# Display_Port.net
KiCad netlist of a schematic drawn in Altium Designer
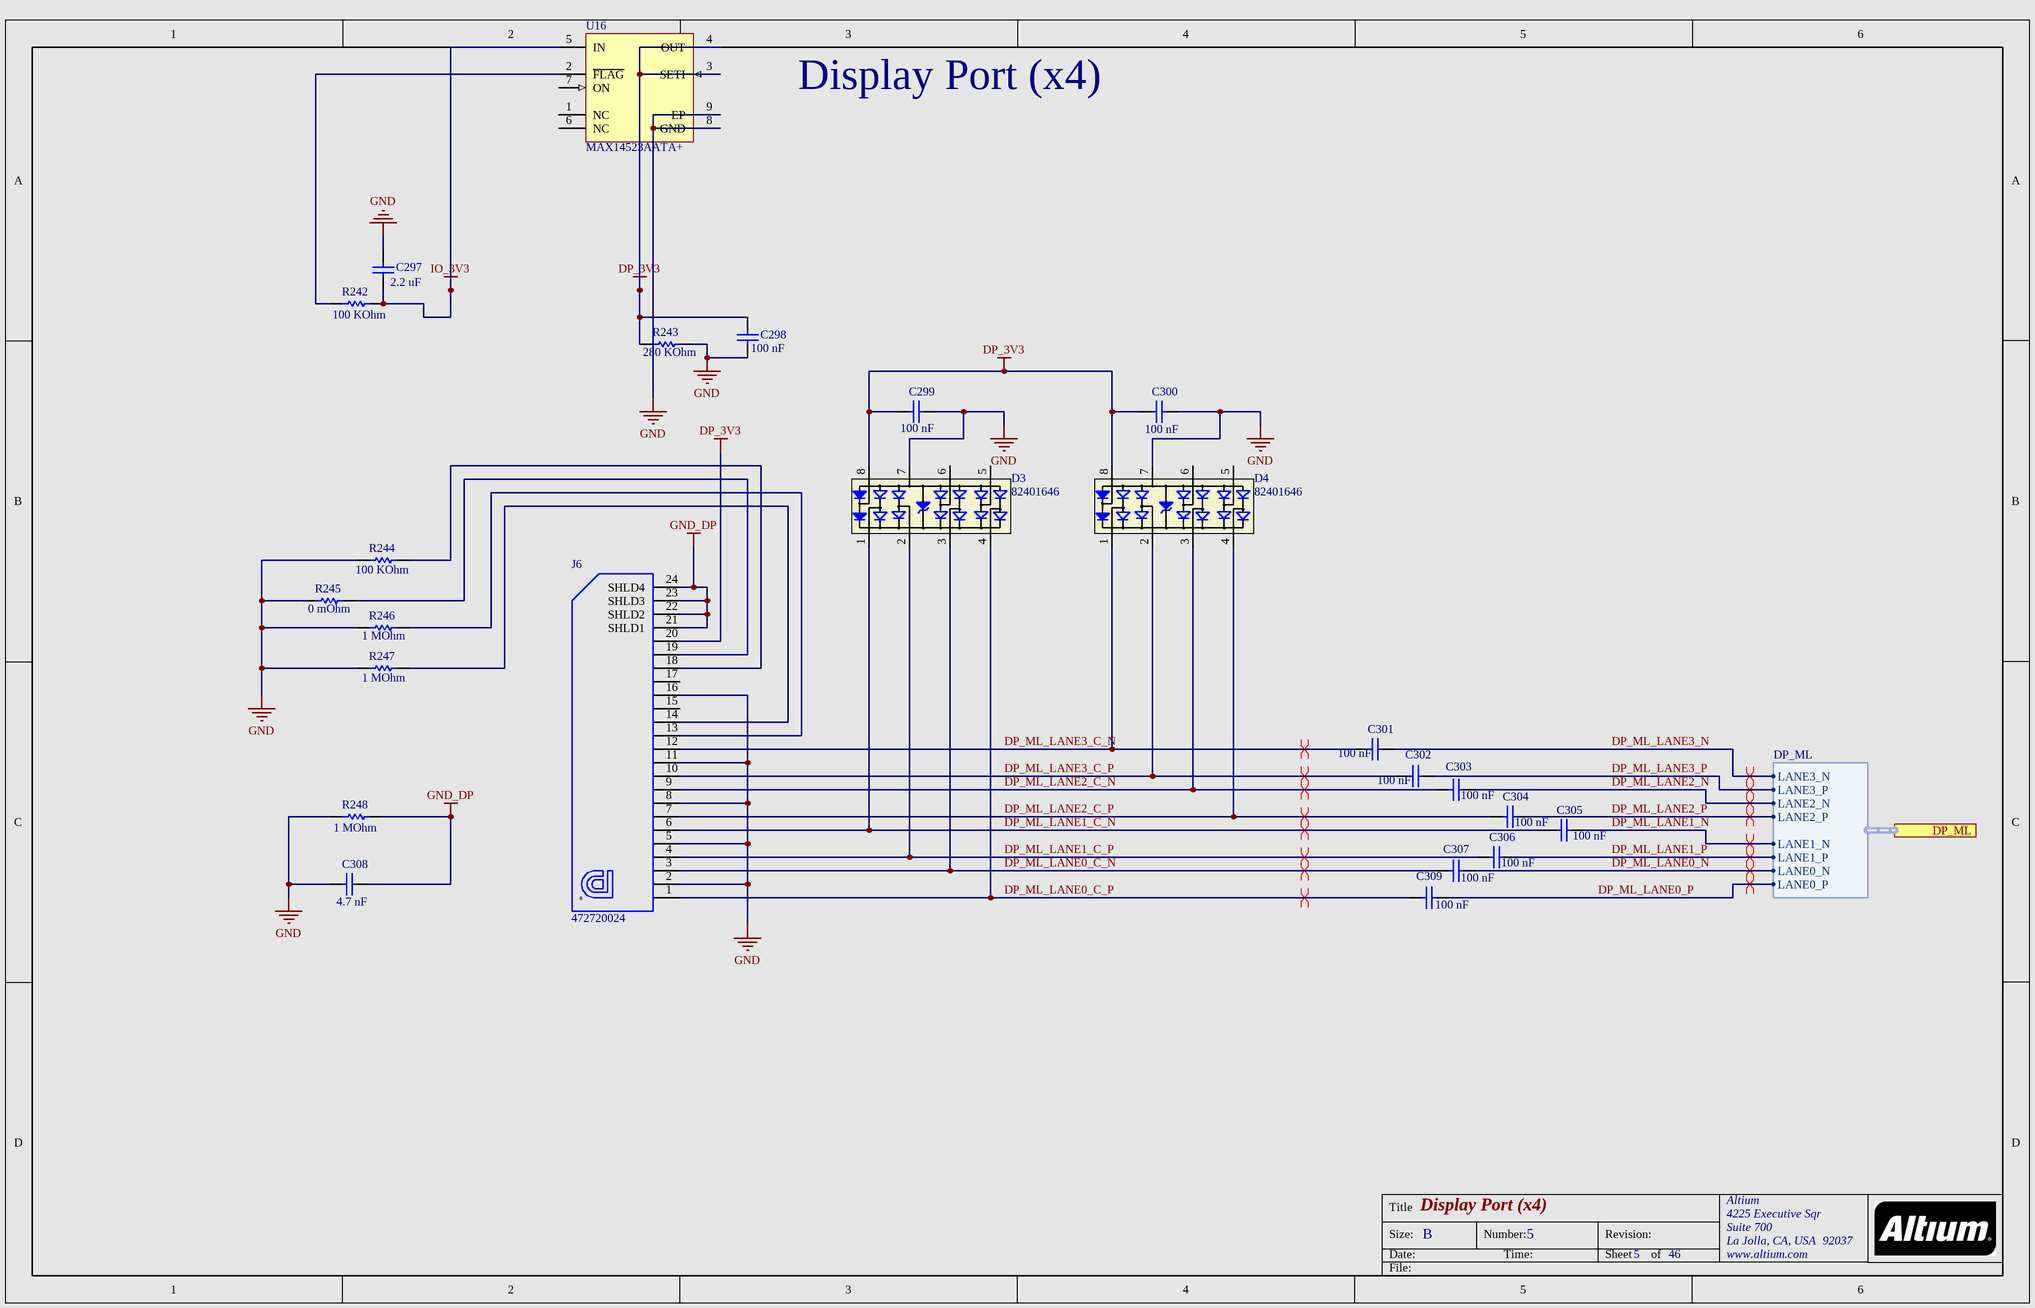
[diagram p0: Display_Port.SchDoc]

(export (version "E")
  (design (tool "Eeschema 10.0.6"))
  (components
    (comp (ref "C297")
      (value "GRM188R61A225KE34x")
      (footprint "CAPC1608X90X35ML10T15")
      (description "Chip Capacitor, 2.2 uF, +/- 10%, 10 V, -55 to 85 degC, 0603 (1608 Metric), RoHS, Tape and Reel")
      (fields (field (name "TOLERANCE") "10%") (field (name "CAPACITANCE") "2.2 uF"))
      (libsource (lib "") (part "CAP-NP-2_1"))
    )
    (comp (ref "C298")
      (value "C1005X7R1E104M")
      (footprint "CAPC1005X55X10LL05")
      (description "Chip Capacitor, 0.1 uF, +/- 20%, 25 V, -55 to 125 degC, 0402 (1005 Metric), RoHS, Tape and Reel")
      (fields (field (name "TOLERANCE") "20%") (field (name "CAPACITANCE") "100 nF"))
      (libsource (lib "Altium Content Vault") (part "CAP-NP-2"))
    )
    (comp (ref "C299")
      (value "C1005X7R1E104M")
      (footprint "CAPC1005X55X10LL05")
      (description "Chip Capacitor, 0.1 uF, +/- 20%, 25 V, -55 to 125 degC, 0402 (1005 Metric), RoHS, Tape and Reel")
      (fields (field (name "TOLERANCE") "20%") (field (name "CAPACITANCE") "100 nF"))
      (libsource (lib "Altium Content Vault") (part "CAP-NP-2"))
    )
    (comp (ref "C300")
      (value "C1005X7R1E104M")
      (footprint "CAPC1005X55X10LL05")
      (description "Chip Capacitor, 0.1 uF, +/- 20%, 25 V, -55 to 125 degC, 0402 (1005 Metric), RoHS, Tape and Reel")
      (fields (field (name "TOLERANCE") "20%") (field (name "CAPACITANCE") "100 nF"))
      (libsource (lib "Altium Content Vault") (part "CAP-NP-2"))
    )
    (comp (ref "C301")
      (value "C1005X7R1E104M")
      (footprint "CAPC1005X55X10LL05")
      (description "Chip Capacitor, 0.1 uF, +/- 20%, 25 V, -55 to 125 degC, 0402 (1005 Metric), RoHS, Tape and Reel")
      (fields (field (name "TOLERANCE") "20%") (field (name "CAPACITANCE") "100 nF"))
      (libsource (lib "Altium Content Vault") (part "CAP-NP-2"))
    )
    (comp (ref "C302")
      (value "C1005X7R1E104M")
      (footprint "CAPC1005X55X10LL05")
      (description "Chip Capacitor, 0.1 uF, +/- 20%, 25 V, -55 to 125 degC, 0402 (1005 Metric), RoHS, Tape and Reel")
      (fields (field (name "TOLERANCE") "20%") (field (name "CAPACITANCE") "100 nF"))
      (libsource (lib "Altium Content Vault") (part "CAP-NP-2"))
    )
    (comp (ref "C303")
      (value "C1005X7R1E104M")
      (footprint "CAPC1005X55X10LL05")
      (description "Chip Capacitor, 0.1 uF, +/- 20%, 25 V, -55 to 125 degC, 0402 (1005 Metric), RoHS, Tape and Reel")
      (fields (field (name "TOLERANCE") "20%") (field (name "CAPACITANCE") "100 nF"))
      (libsource (lib "Altium Content Vault") (part "CAP-NP-2"))
    )
    (comp (ref "C304")
      (value "C1005X7R1E104M")
      (footprint "CAPC1005X55X10LL05")
      (description "Chip Capacitor, 0.1 uF, +/- 20%, 25 V, -55 to 125 degC, 0402 (1005 Metric), RoHS, Tape and Reel")
      (fields (field (name "TOLERANCE") "20%") (field (name "CAPACITANCE") "100 nF"))
      (libsource (lib "Altium Content Vault") (part "CAP-NP-2"))
    )
    (comp (ref "C305")
      (value "C1005X7R1E104M")
      (footprint "CAPC1005X55X10LL05")
      (description "Chip Capacitor, 0.1 uF, +/- 20%, 25 V, -55 to 125 degC, 0402 (1005 Metric), RoHS, Tape and Reel")
      (fields (field (name "TOLERANCE") "20%") (field (name "CAPACITANCE") "100 nF"))
      (libsource (lib "Altium Content Vault") (part "CAP-NP-2"))
    )
    (comp (ref "C306")
      (value "C1005X7R1E104M")
      (footprint "CAPC1005X55X10LL05")
      (description "Chip Capacitor, 0.1 uF, +/- 20%, 25 V, -55 to 125 degC, 0402 (1005 Metric), RoHS, Tape and Reel")
      (fields (field (name "TOLERANCE") "20%") (field (name "CAPACITANCE") "100 nF"))
      (libsource (lib "Altium Content Vault") (part "CAP-NP-2"))
    )
    (comp (ref "C307")
      (value "C1005X7R1E104M")
      (footprint "CAPC1005X55X10LL05")
      (description "Chip Capacitor, 0.1 uF, +/- 20%, 25 V, -55 to 125 degC, 0402 (1005 Metric), RoHS, Tape and Reel")
      (fields (field (name "TOLERANCE") "20%") (field (name "CAPACITANCE") "100 nF"))
      (libsource (lib "Altium Content Vault") (part "CAP-NP-2"))
    )
    (comp (ref "C308")
      (value "GRM155R71H472KA01D")
      (footprint "CAPC1005X55X25NL05T10")
      (description "Chip Capacitor, 4.7 nF, +/- 10%, 50 V, -55 to 125 degC, 0402 (1005 Metric), RoHS, Tape and Reel")
      (fields
        (field (name "TOLERANCE") "10%")
        (field (name "CAPACITANCE") "4.7 nF")
        (field (name "MANUFACTURER") "Basic Passives")
      )
      (libsource (lib "Altium Content Vault") (part "CAP-NP-2"))
    )
    (comp (ref "C309")
      (value "C1005X7R1E104M")
      (footprint "CAPC1005X55X10LL05")
      (description "Chip Capacitor, 0.1 uF, +/- 20%, 25 V, -55 to 125 degC, 0402 (1005 Metric), RoHS, Tape and Reel")
      (fields (field (name "TOLERANCE") "20%") (field (name "CAPACITANCE") "100 nF"))
      (libsource (lib "Altium Content Vault") (part "CAP-NP-2"))
    )
    (comp (ref "D3")
      (value "82401646")
      (footprint "MSOP-8L")
      (description "TVS Diode WE-TVS-SS, VRWM=5V")
      (fields (field (name "MANUFACTURER") "Wuerth Elektronik"))
      (libsource (lib "Altium Content Vault") (part "CMP-1482-00002-1"))
    )
    (comp (ref "D4")
      (value "82401646")
      (footprint "MSOP-8L")
      (description "TVS Diode WE-TVS-SS, VRWM=5V")
      (fields (field (name "MANUFACTURER") "Wuerth Elektronik"))
      (libsource (lib "Altium Content Vault") (part "CMP-1482-00002-1"))
    )
    (comp (ref "J6")
      (value "472720024")
      (footprint "MOLX-472720024_V")
      (fields (field (name "MANUFACTURER") "Molex"))
      (libsource (lib "Altium Content Vault") (part "CMP-1704-00002-1"))
    )
    (comp (ref "R242")
      (value "ERJ-2RKF1003X")
      (footprint "RESC1005X40X25LL05T05")
      (description "Chip Resistor, 100 KOhm, +/- 1%, 100 mW, -55 to 155 degC, 0402 (1005 Metric), RoHS, Tape and Reel")
      (fields
        (field (name "RESISTANCE") "100 KOhm")
        (field (name "TOLERANCE") "1%")
        (field (name "MANUFACTURER") "Basic Passives")
      )
      (libsource (lib "Altium Content Vault") (part "RES-2"))
    )
    (comp (ref "R243")
      (value "ERJ-2RKF2803X")
      (footprint "RESC1005X40X25LL05T05")
      (description "Chip Resistor, 280 KOhm, +/- 1%, 100 mW, -55 to 155 degC, 0402 (1005 Metric), RoHS, Cut Tape")
      (fields
        (field (name "TOLERANCE") "1%")
        (field (name "RESISTANCE") "280 KOhm")
        (field (name "MANUFACTURER") "Basic Passives")
      )
      (libsource (lib "Altium Content Vault") (part "RES-2"))
    )
    (comp (ref "R244")
      (value "ERJ-2RKF1003X")
      (footprint "RESC1005X40X25LL05T05")
      (description "Chip Resistor, 100 KOhm, +/- 1%, 100 mW, -55 to 155 degC, 0402 (1005 Metric), RoHS, Tape and Reel")
      (fields
        (field (name "RESISTANCE") "100 KOhm")
        (field (name "TOLERANCE") "1%")
        (field (name "MANUFACTURER") "Basic Passives")
      )
      (libsource (lib "Altium Content Vault") (part "RES-2"))
    )
    (comp (ref "R245")
      (value "ERJ-2GE0R00X")
      (footprint "RESC1005X40X25ML05T05")
      (description "Chip Resistor, 0 mOhm, +/- 5%, 100 mW, -55 to 155 degC, 0402 (1005 Metric), RoHS, Tape and Reel")
      (fields
        (field (name "TOLERANCE") "5%")
        (field (name "RESISTANCE") "0 mOhm")
        (field (name "MANUFACTURER") "Basic Passives")
      )
      (libsource (lib "Altium Content Vault") (part "RES-2"))
    )
    (comp (ref "R246")
      (value "ERJ-2RKF1004X")
      (footprint "RESC1005X40X25LL05T05")
      (description "Chip Resistor, 1 MOhm, +/- 1%, 100 mW, -55 to 155 degC, 0402 (1005 Metric), RoHS, Tape and Reel")
      (fields
        (field (name "TOLERANCE") "1%")
        (field (name "RESISTANCE") "1 MOhm")
        (field (name "MANUFACTURER") "Basic Passives")
      )
      (libsource (lib "Altium Content Vault") (part "RES-2"))
    )
    (comp (ref "R247")
      (value "ERJ-2RKF1004X")
      (footprint "RESC1005X40X25LL05T05")
      (description "Chip Resistor, 1 MOhm, +/- 1%, 100 mW, -55 to 155 degC, 0402 (1005 Metric), RoHS, Tape and Reel")
      (fields
        (field (name "TOLERANCE") "1%")
        (field (name "RESISTANCE") "1 MOhm")
        (field (name "MANUFACTURER") "Basic Passives")
      )
      (libsource (lib "Altium Content Vault") (part "RES-2"))
    )
    (comp (ref "R248")
      (value "ERJ-2RKF1004X")
      (footprint "RESC1005X40X25LL05T05")
      (description "Chip Resistor, 1 MOhm, +/- 1%, 100 mW, -55 to 155 degC, 0402 (1005 Metric), RoHS, Tape and Reel")
      (fields
        (field (name "TOLERANCE") "1%")
        (field (name "RESISTANCE") "1 MOhm")
        (field (name "MANUFACTURER") "Basic Passives")
      )
      (libsource (lib "Altium Content Vault") (part "RES-2"))
    )
    (comp (ref "U16")
      (value "MAX14523AATA+")
      (footprint "MAXM-T833+2_V")
      (description "Adjustable Current-Limit Switch, 1.7 to 5.5 V, -40 to 125 degC, 8-Pin TDFN (T833+2), RoHS")
      (fields (field (name "MANUFACTURER") "Maxim"))
      (libsource (lib "Altium Content Vault") (part "MAXM-MAX14523A-T833+2-8"))
    )
  )
  (nets
    (net (code "2") (name "/DP_ML_LANE0_C_N") (class "Default")
      (node (ref "C307") (pin "2") (pinfunction "2_2") (pintype "passive"))
      (node (ref "D3") (pin "3") (pinfunction "I/O3_3") (pintype "passive"))
      (node (ref "J6") (pin "3") (pinfunction "3_3") (pintype "passive"))
    )
    (net (code "3") (name "/DP_ML_LANE0_C_P") (class "Default")
      (node (ref "C309") (pin "2") (pinfunction "2_2") (pintype "passive"))
      (node (ref "D3") (pin "4") (pinfunction "I/O4_4") (pintype "passive"))
      (node (ref "J6") (pin "1") (pinfunction "1_1") (pintype "passive"))
    )
    (net (code "4") (name "/DP_ML_LANE0_N") (class "Default")
      (node (ref "C307") (pin "1") (pinfunction "1_1") (pintype "passive"))
    )
    (net (code "5") (name "/DP_ML_LANE0_P") (class "Default")
      (node (ref "C309") (pin "1") (pinfunction "1_1") (pintype "passive"))
    )
    (net (code "6") (name "/DP_ML_LANE1_C_N") (class "Default")
      (node (ref "C305") (pin "2") (pinfunction "2_2") (pintype "passive"))
      (node (ref "D3") (pin "1") (pinfunction "I/O1_1") (pintype "passive"))
      (node (ref "J6") (pin "6") (pinfunction "6_6") (pintype "passive"))
    )
    (net (code "7") (name "/DP_ML_LANE1_C_P") (class "Default")
      (node (ref "C306") (pin "2") (pinfunction "2_2") (pintype "passive"))
      (node (ref "D3") (pin "2") (pinfunction "I/O2_2") (pintype "passive"))
      (node (ref "J6") (pin "4") (pinfunction "4_4") (pintype "passive"))
    )
    (net (code "8") (name "/DP_ML_LANE1_N") (class "Default")
      (node (ref "C305") (pin "1") (pinfunction "1_1") (pintype "passive"))
    )
    (net (code "9") (name "/DP_ML_LANE1_P") (class "Default")
      (node (ref "C306") (pin "1") (pinfunction "1_1") (pintype "passive"))
    )
    (net (code "10") (name "/DP_ML_LANE2_C_N") (class "Default")
      (node (ref "C303") (pin "2") (pinfunction "2_2") (pintype "passive"))
      (node (ref "D4") (pin "3") (pinfunction "I/O3_3") (pintype "passive"))
      (node (ref "J6") (pin "9") (pinfunction "9_9") (pintype "passive"))
    )
    (net (code "11") (name "/DP_ML_LANE2_C_P") (class "Default")
      (node (ref "C304") (pin "2") (pinfunction "2_2") (pintype "passive"))
      (node (ref "D4") (pin "4") (pinfunction "I/O4_4") (pintype "passive"))
      (node (ref "J6") (pin "7") (pinfunction "7_7") (pintype "passive"))
    )
    (net (code "12") (name "/DP_ML_LANE2_N") (class "Default")
      (node (ref "C303") (pin "1") (pinfunction "1_1") (pintype "passive"))
    )
    (net (code "13") (name "/DP_ML_LANE2_P") (class "Default")
      (node (ref "C304") (pin "1") (pinfunction "1_1") (pintype "passive"))
    )
    (net (code "14") (name "/DP_ML_LANE3_C_N") (class "Default")
      (node (ref "C301") (pin "2") (pinfunction "2_2") (pintype "passive"))
      (node (ref "D4") (pin "1") (pinfunction "I/O1_1") (pintype "passive"))
      (node (ref "J6") (pin "12") (pinfunction "12_12") (pintype "passive"))
    )
    (net (code "15") (name "/DP_ML_LANE3_C_P") (class "Default")
      (node (ref "C302") (pin "2") (pinfunction "2_2") (pintype "passive"))
      (node (ref "D4") (pin "2") (pinfunction "I/O2_2") (pintype "passive"))
      (node (ref "J6") (pin "10") (pinfunction "10_10") (pintype "passive"))
    )
    (net (code "16") (name "/DP_ML_LANE3_N") (class "Default")
      (node (ref "C301") (pin "1") (pinfunction "1_1") (pintype "passive"))
    )
    (net (code "17") (name "/DP_ML_LANE3_P") (class "Default")
      (node (ref "C302") (pin "1") (pinfunction "1_1") (pintype "passive"))
    )
    (net (code "19") (name "DP_3V3") (class "Default")
      (node (ref "C298") (pin "2") (pinfunction "2_2") (pintype "passive"))
      (node (ref "C299") (pin "2") (pinfunction "2_2") (pintype "passive"))
      (node (ref "C300") (pin "2") (pinfunction "2_2") (pintype "passive"))
      (node (ref "D3") (pin "8") (pinfunction "VDD_8") (pintype "passive"))
      (node (ref "D4") (pin "8") (pinfunction "VDD_8") (pintype "passive"))
      (node (ref "J6") (pin "20") (pinfunction "20_20") (pintype "passive"))
      (node (ref "R243") (pin "1") (pinfunction "1_1") (pintype "passive"))
      (node (ref "U16") (pin "3") (pinfunction "SETI_3") (pintype "input"))
      (node (ref "U16") (pin "4") (pinfunction "OUT_4") (pintype "power_in"))
    )
    (net (code "20") (name "GND") (class "Default")
      (node (ref "C297") (pin "2") (pinfunction "2_2") (pintype "passive"))
      (node (ref "C298") (pin "1") (pinfunction "1_1") (pintype "passive"))
      (node (ref "C299") (pin "1") (pinfunction "1_1") (pintype "passive"))
      (node (ref "C300") (pin "1") (pinfunction "1_1") (pintype "passive"))
      (node (ref "C308") (pin "1") (pinfunction "1_1") (pintype "passive"))
      (node (ref "D3") (pin "7") (pinfunction "GND_7") (pintype "passive"))
      (node (ref "D4") (pin "7") (pinfunction "GND_7") (pintype "passive"))
      (node (ref "J6") (pin "11") (pinfunction "11_11") (pintype "passive"))
      (node (ref "J6") (pin "16") (pinfunction "16_16") (pintype "passive"))
      (node (ref "J6") (pin "2") (pinfunction "2_2") (pintype "passive"))
      (node (ref "J6") (pin "5") (pinfunction "5_5") (pintype "passive"))
      (node (ref "J6") (pin "8") (pinfunction "8_8") (pintype "passive"))
      (node (ref "R243") (pin "2") (pinfunction "2_2") (pintype "passive"))
      (node (ref "R244") (pin "1") (pinfunction "1_1") (pintype "passive"))
      (node (ref "R245") (pin "1") (pinfunction "1_1") (pintype "passive"))
      (node (ref "R246") (pin "1") (pinfunction "1_1") (pintype "passive"))
      (node (ref "R247") (pin "1") (pinfunction "1_1") (pintype "passive"))
      (node (ref "R248") (pin "1") (pinfunction "1_1") (pintype "passive"))
      (node (ref "U16") (pin "8") (pinfunction "GND_8") (pintype "power_in"))
      (node (ref "U16") (pin "9") (pinfunction "EP_9") (pintype "power_in"))
    )
    (net (code "21") (name "GND_DP") (class "Default")
      (node (ref "C308") (pin "2") (pinfunction "2_2") (pintype "passive"))
      (node (ref "J6") (pin "21") (pinfunction "SHLD1_21") (pintype "passive"))
      (node (ref "J6") (pin "22") (pinfunction "SHLD2_22") (pintype "passive"))
      (node (ref "J6") (pin "23") (pinfunction "SHLD3_23") (pintype "passive"))
      (node (ref "J6") (pin "24") (pinfunction "SHLD4_24") (pintype "passive"))
      (node (ref "R248") (pin "2") (pinfunction "2_2") (pintype "passive"))
    )
    (net (code "22") (name "IO_3V3") (class "Default")
      (node (ref "C297") (pin "1") (pinfunction "1_1") (pintype "passive"))
      (node (ref "R242") (pin "2") (pinfunction "2_2") (pintype "passive"))
      (node (ref "U16") (pin "5") (pinfunction "IN_5") (pintype "power_in"))
    )
    (net (code "23") (name "Net-(J6-Pad13)") (class "Default")
      (node (ref "J6") (pin "13") (pinfunction "13_13") (pintype "passive"))
      (node (ref "R246") (pin "2") (pinfunction "2_2") (pintype "passive"))
    )
    (net (code "24") (name "Net-(J6-Pad14)") (class "Default")
      (node (ref "J6") (pin "14") (pinfunction "14_14") (pintype "passive"))
      (node (ref "R247") (pin "2") (pinfunction "2_2") (pintype "passive"))
    )
    (net (code "25") (name "Net-(J6-Pad18)") (class "Default")
      (node (ref "J6") (pin "18") (pinfunction "18_18") (pintype "passive"))
      (node (ref "R244") (pin "2") (pinfunction "2_2") (pintype "passive"))
    )
    (net (code "26") (name "Net-(J6-Pad19)") (class "Default")
      (node (ref "J6") (pin "19") (pinfunction "19_19") (pintype "passive"))
      (node (ref "R245") (pin "2") (pinfunction "2_2") (pintype "passive"))
    )
    (net (code "27") (name "Net-(U16-~{FLAG})") (class "Default")
      (node (ref "R242") (pin "1") (pinfunction "1_1") (pintype "passive"))
      (node (ref "U16") (pin "2") (pinfunction "~{FLAG}_2") (pintype "open_collector"))
    )
    (net (code "28") (name "unconnected-(D3-I{slash}O5-Pad5)") (class "Default")
      (node (ref "D3") (pin "5") (pinfunction "I/O5_5") (pintype "passive"))
    )
    (net (code "29") (name "unconnected-(D3-I{slash}O6-Pad6)") (class "Default")
      (node (ref "D3") (pin "6") (pinfunction "I/O6_6") (pintype "passive"))
    )
    (net (code "30") (name "unconnected-(D4-I{slash}O5-Pad5)") (class "Default")
      (node (ref "D4") (pin "5") (pinfunction "I/O5_5") (pintype "passive"))
    )
    (net (code "31") (name "unconnected-(D4-I{slash}O6-Pad6)") (class "Default")
      (node (ref "D4") (pin "6") (pinfunction "I/O6_6") (pintype "passive"))
    )
    (net (code "32") (name "unconnected-(J6-Pad15)") (class "Default")
      (node (ref "J6") (pin "15") (pinfunction "15_15") (pintype "passive"))
    )
    (net (code "33") (name "unconnected-(J6-Pad17)") (class "Default")
      (node (ref "J6") (pin "17") (pinfunction "17_17") (pintype "passive"))
    )
    (net (code "34") (name "unconnected-(U16-NC-Pad1)") (class "Default")
      (node (ref "U16") (pin "1") (pinfunction "NC_1") (pintype "passive"))
    )
    (net (code "35") (name "unconnected-(U16-NC-Pad6)") (class "Default")
      (node (ref "U16") (pin "6") (pinfunction "NC_6") (pintype "passive"))
    )
    (net (code "36") (name "unconnected-(U16-ON-Pad7)") (class "Default")
      (node (ref "U16") (pin "7") (pinfunction "ON_7") (pintype "input"))
    )
  )
)
